# test_subject.net
KiCad netlist of a schematic drawn in EAGLE
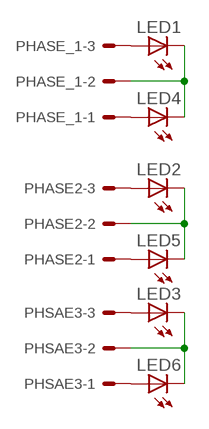
[diagram p0: schematic, sheet 1]

(export (version "E")
  (design (tool "Eeschema 10.0.6"))
  (components
    (comp (ref "LED1")
      (value "LED5MM")
      (footprint "eagle-import:LED5MM")
      (libsource (lib "eagle-import") (part "LED5MM"))
    )
    (comp (ref "LED2")
      (value "LED5MM")
      (footprint "eagle-import:LED5MM")
      (libsource (lib "eagle-import") (part "LED5MM"))
    )
    (comp (ref "LED3")
      (value "LED5MM")
      (footprint "eagle-import:LED5MM")
      (libsource (lib "eagle-import") (part "LED5MM"))
    )
    (comp (ref "LED4")
      (value "LED5MM")
      (footprint "eagle-import:LED5MM")
      (libsource (lib "eagle-import") (part "LED5MM"))
    )
    (comp (ref "LED5")
      (value "LED5MM")
      (footprint "eagle-import:LED5MM")
      (libsource (lib "eagle-import") (part "LED5MM"))
    )
    (comp (ref "LED6")
      (value "LED5MM")
      (footprint "eagle-import:LED5MM")
      (libsource (lib "eagle-import") (part "LED5MM"))
    )
    (comp (ref "PHASE2")
      (value "22-27-2031-03")
      (footprint "eagle-import:6410-03")
      (libsource (lib "eagle-import") (part "22-?-0327-2031"))
    )
    (comp (ref "PHASE_1")
      (value "22-27-2031-03")
      (footprint "eagle-import:6410-03")
      (libsource (lib "eagle-import") (part "22-?-0327-2031"))
    )
    (comp (ref "PHSAE3")
      (value "22-27-2031-03")
      (footprint "eagle-import:6410-03")
      (libsource (lib "eagle-import") (part "22-?-0327-2031"))
    )
  )
  (nets
    (net (code "1") (name "Net-(LED1-C)") (class "Default")
      (node (ref "LED1") (pin "K") (pinfunction "C_K") (pintype "passive"))
      (node (ref "LED4") (pin "K") (pinfunction "C_K") (pintype "passive"))
      (node (ref "PHASE_1") (pin "2") (pinfunction "S_2") (pintype "passive"))
    )
    (net (code "2") (name "Net-(LED2-C)") (class "Default")
      (node (ref "LED2") (pin "K") (pinfunction "C_K") (pintype "passive"))
      (node (ref "LED5") (pin "K") (pinfunction "C_K") (pintype "passive"))
      (node (ref "PHASE2") (pin "2") (pinfunction "S_2") (pintype "passive"))
    )
    (net (code "3") (name "Net-(LED3-C)") (class "Default")
      (node (ref "LED3") (pin "K") (pinfunction "C_K") (pintype "passive"))
      (node (ref "LED6") (pin "K") (pinfunction "C_K") (pintype "passive"))
      (node (ref "PHSAE3") (pin "2") (pinfunction "S_2") (pintype "passive"))
    )
    (net (code "4") (name "Net-(PHASE2A-S)") (class "Default")
      (node (ref "LED5") (pin "A") (pinfunction "A_A") (pintype "passive"))
      (node (ref "PHASE2") (pin "1") (pinfunction "S_1") (pintype "passive"))
    )
    (net (code "5") (name "Net-(PHASE2C-S)") (class "Default")
      (node (ref "LED2") (pin "A") (pinfunction "A_A") (pintype "passive"))
      (node (ref "PHASE2") (pin "3") (pinfunction "S_3") (pintype "passive"))
    )
    (net (code "6") (name "Net-(PHASE_1A-S)") (class "Default")
      (node (ref "LED4") (pin "A") (pinfunction "A_A") (pintype "passive"))
      (node (ref "PHASE_1") (pin "1") (pinfunction "S_1") (pintype "passive"))
    )
    (net (code "7") (name "Net-(PHASE_1C-S)") (class "Default")
      (node (ref "LED1") (pin "A") (pinfunction "A_A") (pintype "passive"))
      (node (ref "PHASE_1") (pin "3") (pinfunction "S_3") (pintype "passive"))
    )
    (net (code "8") (name "Net-(PHSAE3A-S)") (class "Default")
      (node (ref "LED6") (pin "A") (pinfunction "A_A") (pintype "passive"))
      (node (ref "PHSAE3") (pin "1") (pinfunction "S_1") (pintype "passive"))
    )
    (net (code "9") (name "Net-(PHSAE3C-S)") (class "Default")
      (node (ref "LED3") (pin "A") (pinfunction "A_A") (pintype "passive"))
      (node (ref "PHSAE3") (pin "3") (pinfunction "S_3") (pintype "passive"))
    )
  )
)
